# Volume_Control.net
KiCad netlist of a schematic drawn in EAGLE
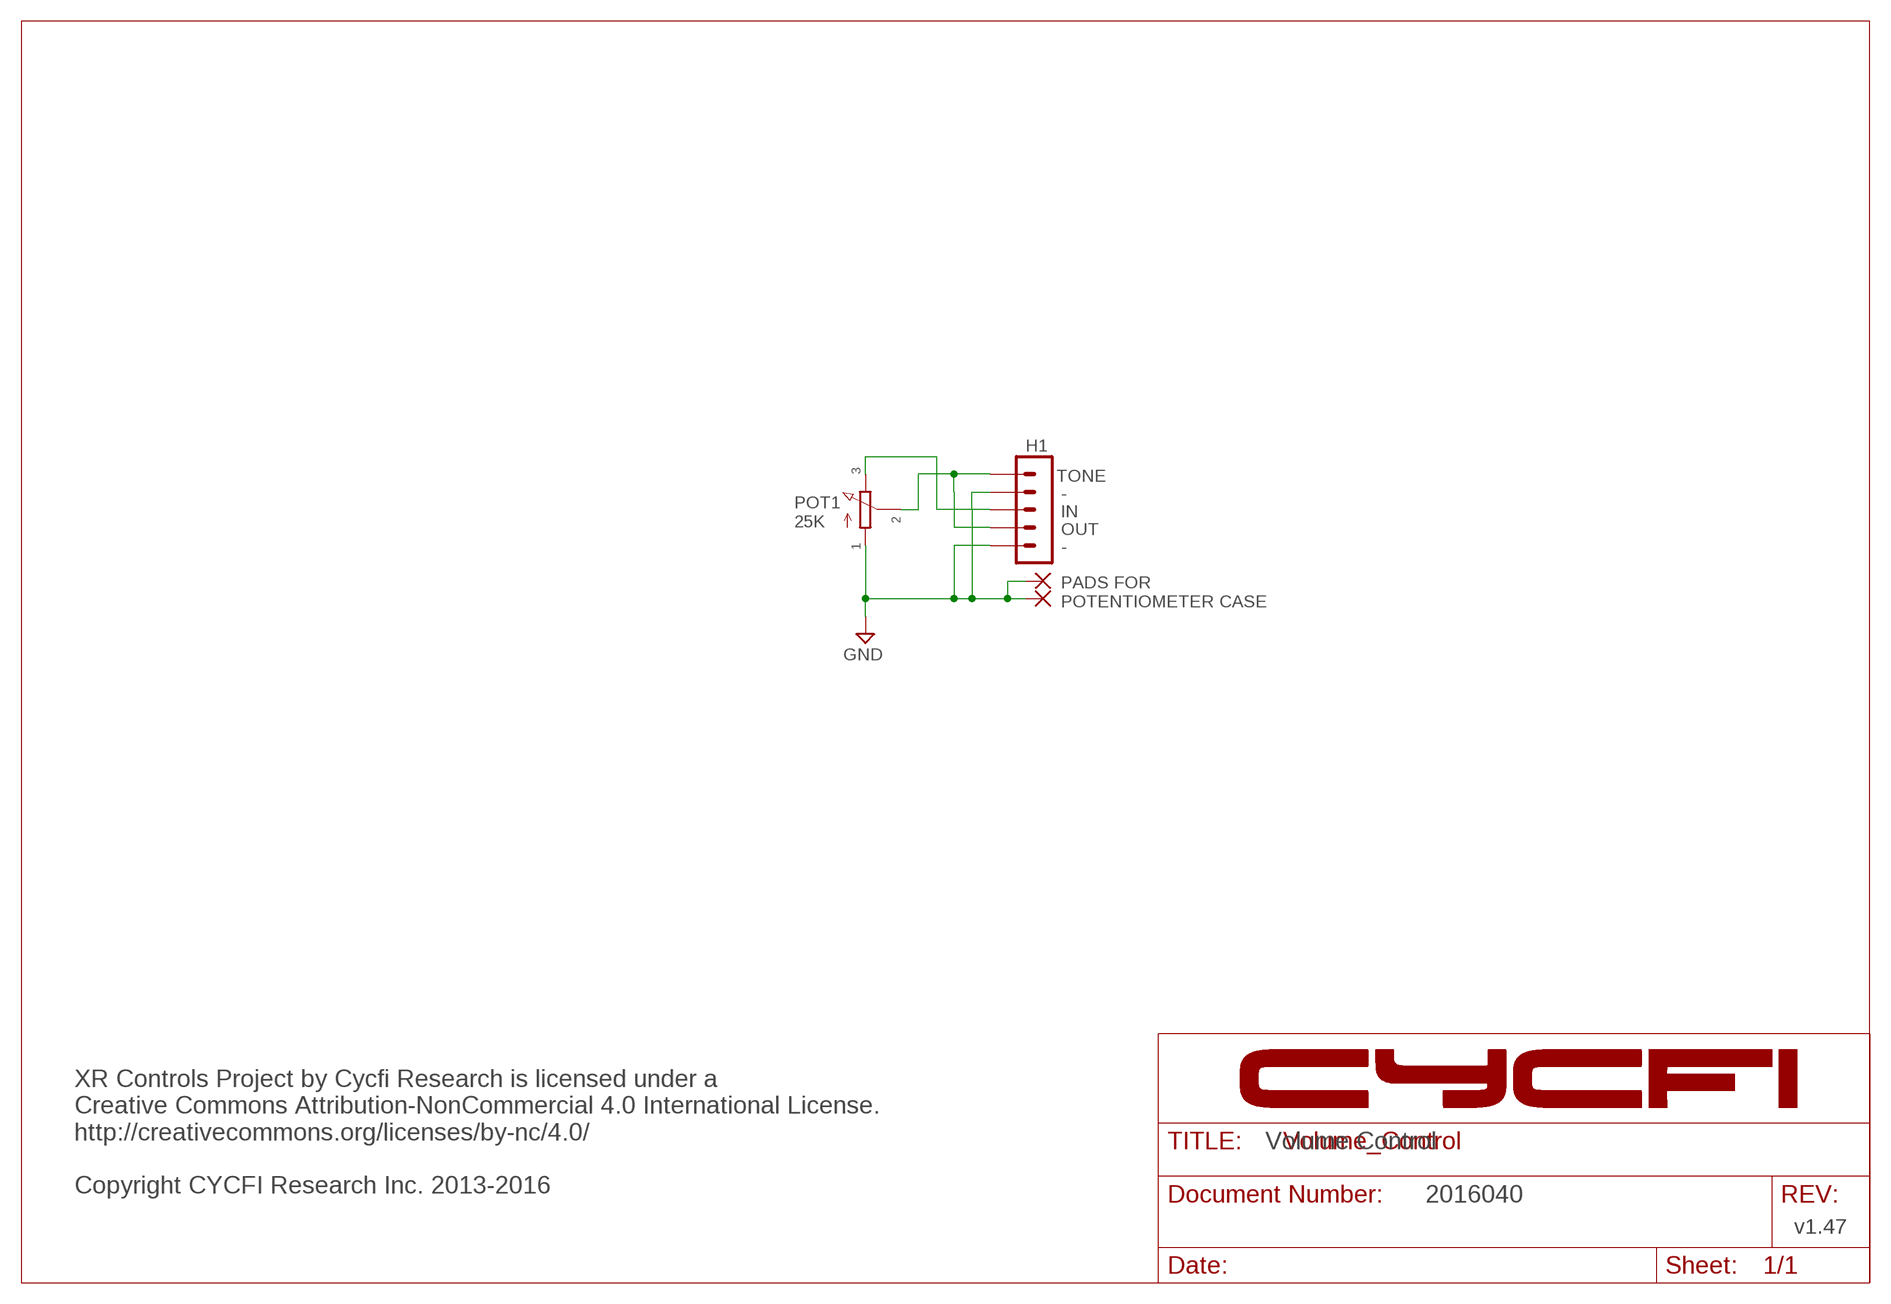
[diagram p0: schematic, sheet 1]

(export (version "E")
  (design (tool "Eeschema 10.0.6"))
  (components
    (comp (ref "GND3")
      (value "SMD2")
      (footprint "eagle-import:SMD1,27-2,54")
      (libsource (lib "eagle-import") (part "SMD2"))
    )
    (comp (ref "GND4")
      (value "SMD2")
      (footprint "eagle-import:SMD1,27-2,54")
      (libsource (lib "eagle-import") (part "SMD2"))
    )
    (comp (ref "H1")
      (value "961105-5500-AR-PR")
      (footprint "eagle-import:5P-SMD-2.54MM")
      (libsource (lib "eagle-import") (part "961105-5500-AR-PR"))
    )
    (comp (ref "POT1")
      (value "PDB241-GTR01")
      (footprint "eagle-import:PDB241")
      (libsource (lib "eagle-import") (part "PDB241-GTR01"))
    )
  )
  (nets
    (net (code "1") (name "GND") (class "Default")
      (node (ref "GND3") (pin "1") (pinfunction "P_1") (pintype "passive"))
      (node (ref "GND4") (pin "1") (pinfunction "P_1") (pintype "passive"))
      (node (ref "H1") (pin "P$1") (pinfunction "P$1_P$1") (pintype "bidirectional"))
      (node (ref "H1") (pin "P$4") (pinfunction "P$4_P$4") (pintype "bidirectional"))
      (node (ref "POT1") (pin "P$1") (pinfunction "1_P$1") (pintype "passive"))
    )
    (net (code "2") (name "Net-(POT1-2)") (class "Default")
      (node (ref "H1") (pin "P$2") (pinfunction "P$2_P$2") (pintype "bidirectional"))
      (node (ref "H1") (pin "P$5") (pinfunction "P$5_P$5") (pintype "bidirectional"))
      (node (ref "POT1") (pin "P$2") (pinfunction "2_P$2") (pintype "passive"))
    )
    (net (code "3") (name "Net-(POT1-3)") (class "Default")
      (node (ref "H1") (pin "P$3") (pinfunction "P$3_P$3") (pintype "bidirectional"))
      (node (ref "POT1") (pin "P$3") (pinfunction "3_P$3") (pintype "passive"))
    )
  )
)
